# RumiCarGen3-Sensor4.net
KiCad netlist of a schematic drawn in EAGLE
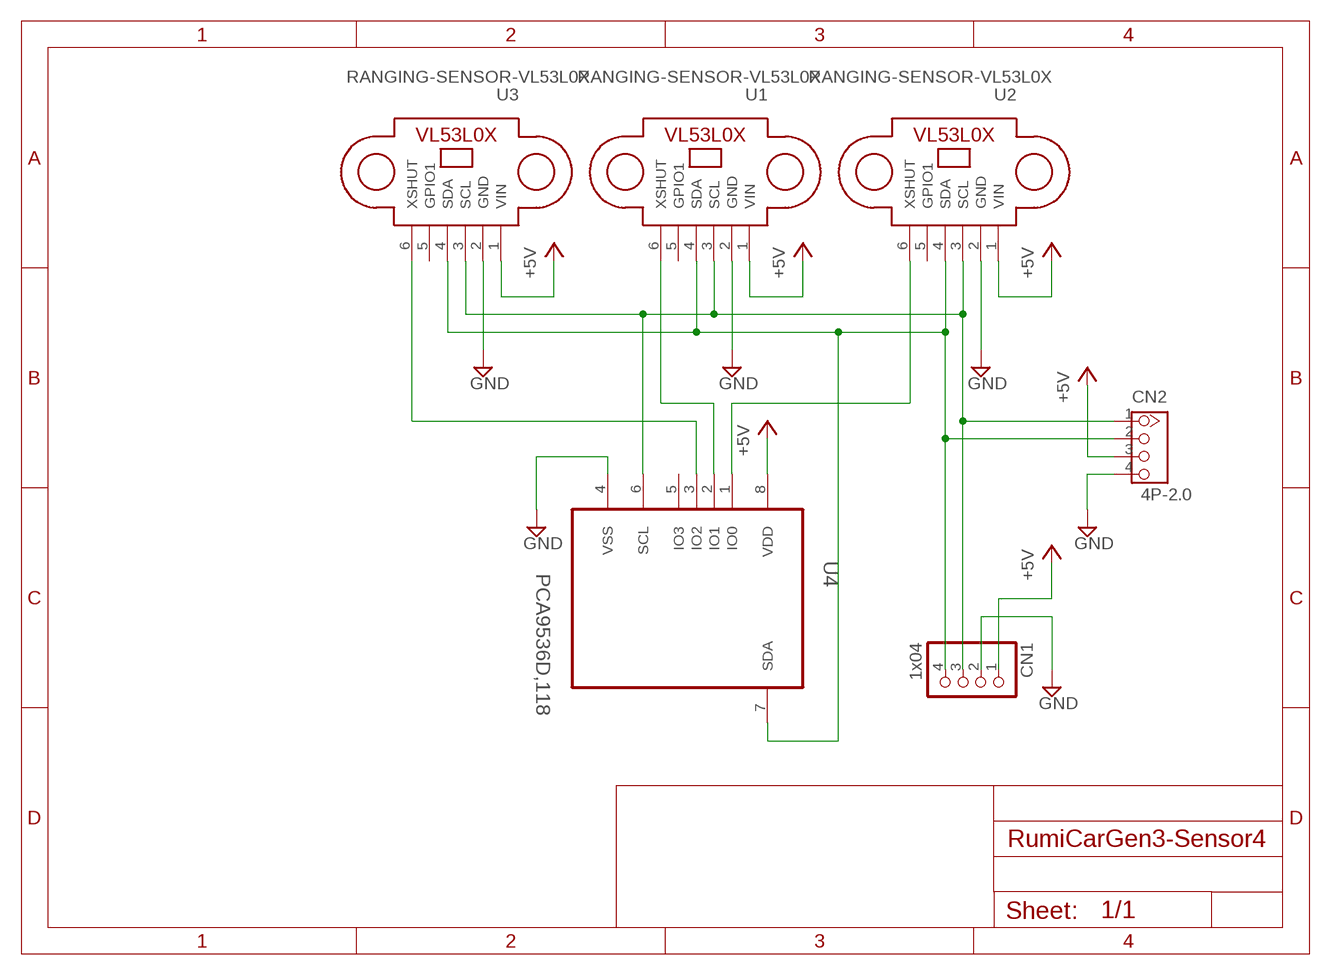
[diagram p0: schematic, sheet 1]

(export (version "E")
  (design (tool "Eeschema 10.0.6"))
  (components
    (comp (ref "CN1")
      (value "1x04")
      (footprint "eagle-import:1X04")
      (libsource (lib "eagle-import") (part "PINHD-1X4"))
    )
    (comp (ref "CN2")
      (value "4P-2.0")
      (footprint "eagle-import:HW4-2.0")
      (libsource (lib "eagle-import") (part "GROVE-CONNECTOR-DIP(4P-2.0)"))
    )
    (comp (ref "U1")
      (value "RANGING-SENSOR-VL53L0X")
      (footprint "eagle-import:RANGING-SENSOR-VL53L0X")
      (libsource (lib "eagle-import") (part "RANGING-SENSOR-VL53L0X"))
    )
    (comp (ref "U2")
      (value "RANGING-SENSOR-VL53L0X")
      (footprint "eagle-import:RANGING-SENSOR-VL53L0X")
      (libsource (lib "eagle-import") (part "RANGING-SENSOR-VL53L0X"))
    )
    (comp (ref "U3")
      (value "RANGING-SENSOR-VL53L0X")
      (footprint "eagle-import:RANGING-SENSOR-VL53L0X")
      (libsource (lib "eagle-import") (part "RANGING-SENSOR-VL53L0X"))
    )
    (comp (ref "U4")
      (value "PCA9536D,118")
      (footprint "eagle-import:SOIC127P600X175-8N")
      (fields (field (name "MF") "NXP USA"))
      (libsource (lib "eagle-import") (part "PCA9536D,118"))
    )
  )
  (nets
    (net (code "1") (name "+5V") (class "Default")
      (node (ref "CN1") (pin "1") (pinfunction "1_1") (pintype "passive"))
      (node (ref "CN2") (pin "3") (pinfunction "3_3") (pintype "bidirectional"))
      (node (ref "U1") (pin "1") (pinfunction "VIN_1") (pintype "power_in"))
      (node (ref "U2") (pin "1") (pinfunction "VIN_1") (pintype "power_in"))
      (node (ref "U3") (pin "1") (pinfunction "VIN_1") (pintype "power_in"))
      (node (ref "U4") (pin "8") (pinfunction "VDD_8") (pintype "power_in"))
    )
    (net (code "2") (name "GND") (class "Default")
      (node (ref "CN1") (pin "2") (pinfunction "2_2") (pintype "passive"))
      (node (ref "CN2") (pin "4") (pinfunction "4_4") (pintype "bidirectional"))
      (node (ref "U1") (pin "2") (pinfunction "GND_2") (pintype "power_in"))
      (node (ref "U2") (pin "2") (pinfunction "GND_2") (pintype "power_in"))
      (node (ref "U3") (pin "2") (pinfunction "GND_2") (pintype "power_in"))
      (node (ref "U4") (pin "4") (pinfunction "VSS_4") (pintype "power_in"))
    )
    (net (code "3") (name "Net-(U1-SCL)") (class "Default")
      (node (ref "CN1") (pin "3") (pinfunction "3_3") (pintype "passive"))
      (node (ref "CN2") (pin "1") (pinfunction "1_1") (pintype "bidirectional"))
      (node (ref "U1") (pin "3") (pinfunction "SCL_3") (pintype "bidirectional"))
      (node (ref "U2") (pin "3") (pinfunction "SCL_3") (pintype "bidirectional"))
      (node (ref "U3") (pin "3") (pinfunction "SCL_3") (pintype "bidirectional"))
      (node (ref "U4") (pin "6") (pinfunction "SCL_6") (pintype "input"))
    )
    (net (code "4") (name "Net-(U1-SDA)") (class "Default")
      (node (ref "CN1") (pin "4") (pinfunction "4_4") (pintype "passive"))
      (node (ref "CN2") (pin "2") (pinfunction "2_2") (pintype "bidirectional"))
      (node (ref "U1") (pin "4") (pinfunction "SDA_4") (pintype "bidirectional"))
      (node (ref "U2") (pin "4") (pinfunction "SDA_4") (pintype "bidirectional"))
      (node (ref "U3") (pin "4") (pinfunction "SDA_4") (pintype "bidirectional"))
      (node (ref "U4") (pin "7") (pinfunction "SDA_7") (pintype "bidirectional"))
    )
    (net (code "5") (name "Net-(U1-XSHUT)") (class "Default")
      (node (ref "U1") (pin "6") (pinfunction "XSHUT_6") (pintype "bidirectional"))
      (node (ref "U4") (pin "2") (pinfunction "IO1_2") (pintype "bidirectional"))
    )
    (net (code "6") (name "Net-(U2-XSHUT)") (class "Default")
      (node (ref "U2") (pin "6") (pinfunction "XSHUT_6") (pintype "bidirectional"))
      (node (ref "U4") (pin "1") (pinfunction "IO0_1") (pintype "bidirectional"))
    )
    (net (code "7") (name "Net-(U3-XSHUT)") (class "Default")
      (node (ref "U3") (pin "6") (pinfunction "XSHUT_6") (pintype "bidirectional"))
      (node (ref "U4") (pin "3") (pinfunction "IO2_3") (pintype "bidirectional"))
    )
    (net (code "8") (name "unconnected-(U1-GPIO1-Pad5)") (class "Default")
      (node (ref "U1") (pin "5") (pinfunction "GPIO1_5") (pintype "bidirectional"))
    )
    (net (code "9") (name "unconnected-(U2-GPIO1-Pad5)") (class "Default")
      (node (ref "U2") (pin "5") (pinfunction "GPIO1_5") (pintype "bidirectional"))
    )
    (net (code "10") (name "unconnected-(U3-GPIO1-Pad5)") (class "Default")
      (node (ref "U3") (pin "5") (pinfunction "GPIO1_5") (pintype "bidirectional"))
    )
    (net (code "11") (name "unconnected-(U4-IO3-Pad5)") (class "Default")
      (node (ref "U4") (pin "5") (pinfunction "IO3_5") (pintype "bidirectional"))
    )
  )
)
